# open-lab-VUSB-A.net
KiCad netlist of a schematic drawn in EAGLE
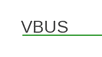
[diagram p0: schematic, sheet 1, part 1 of 2]
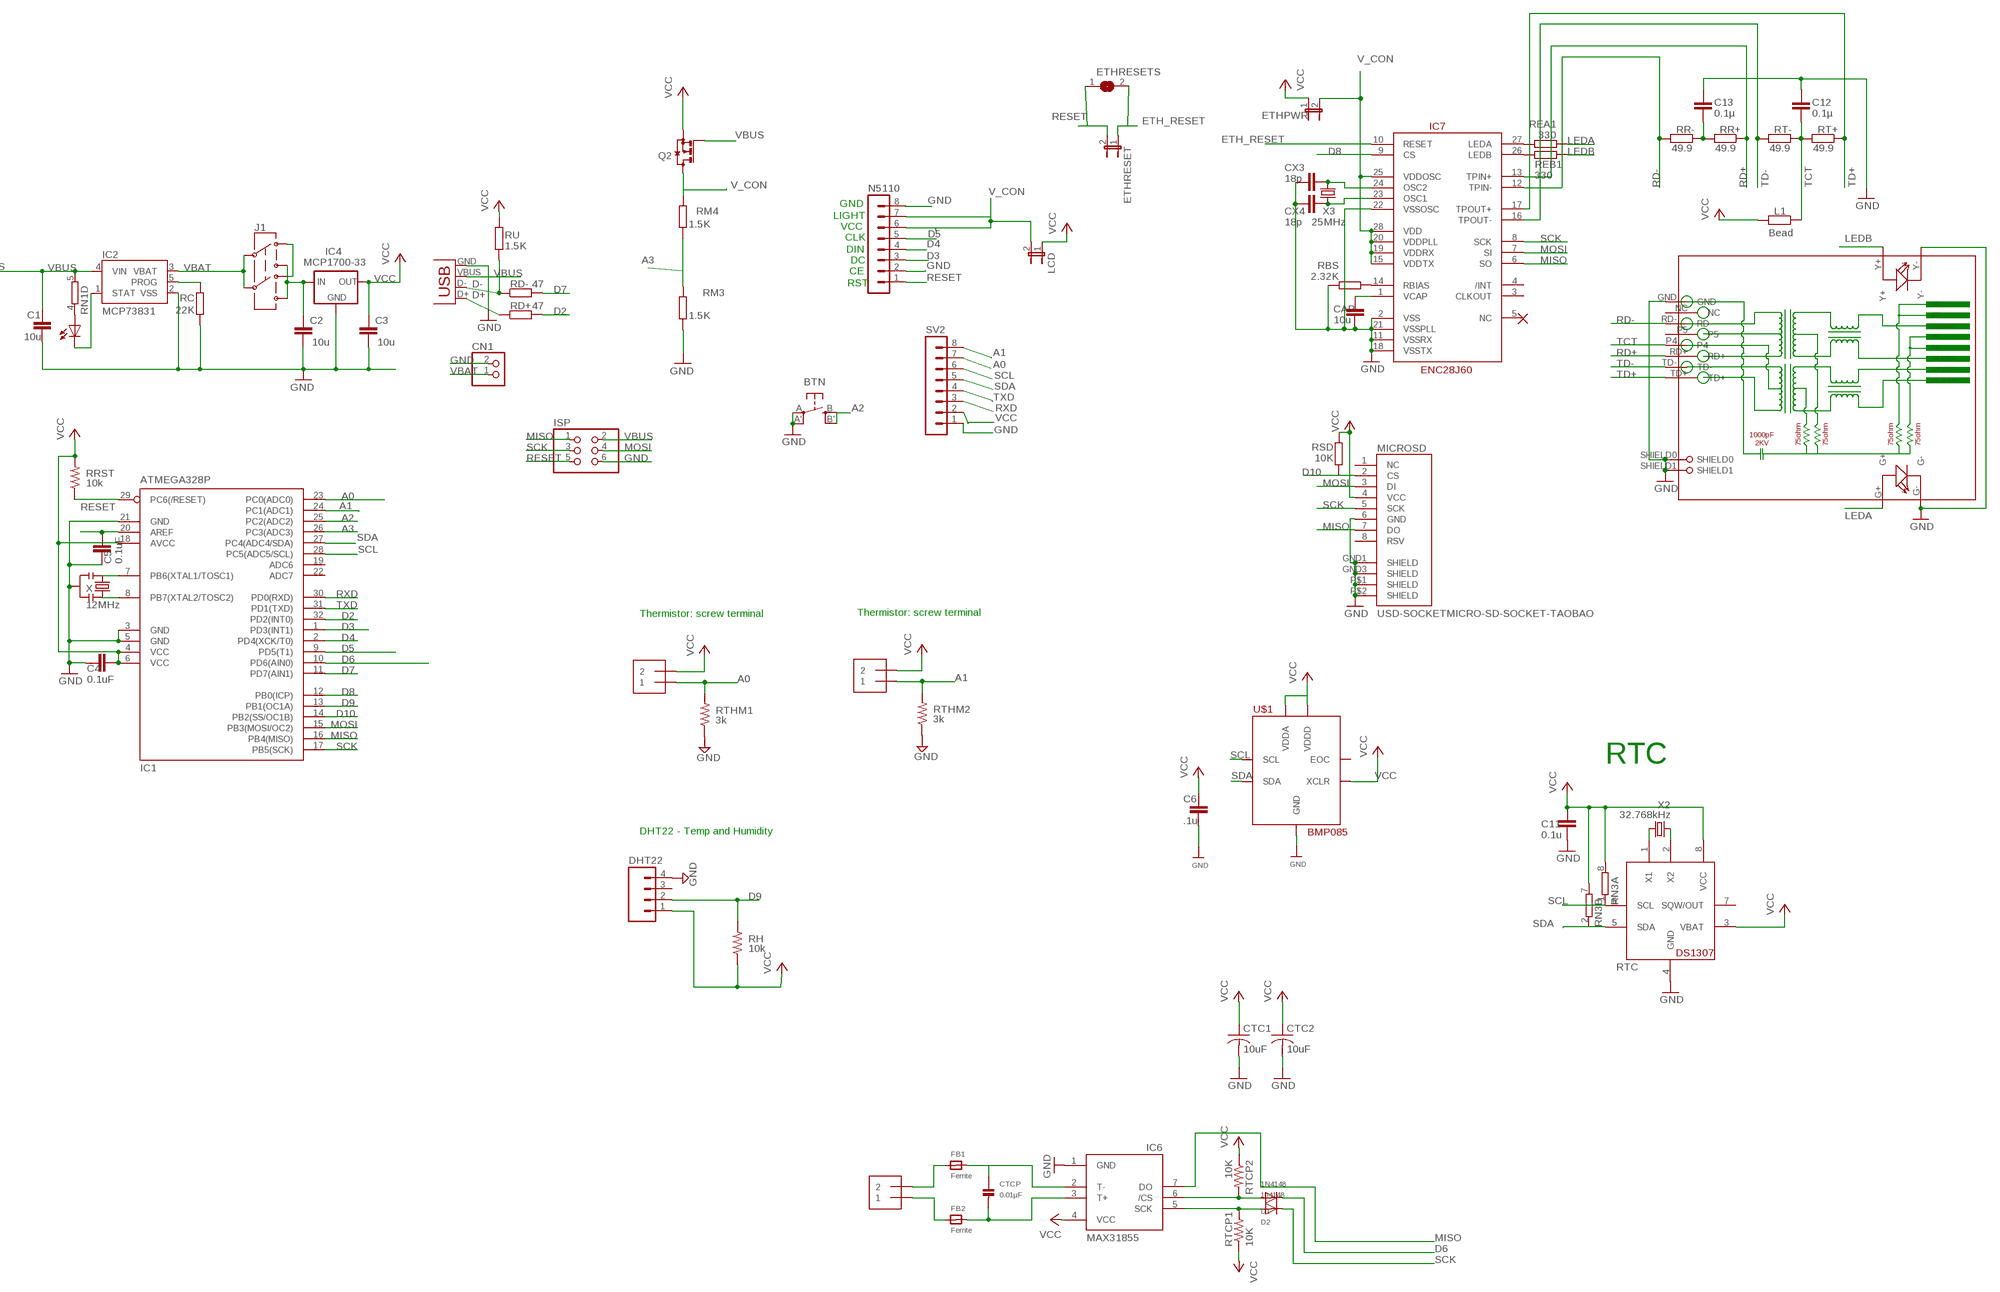
[diagram p1: schematic, sheet 1, part 2 of 2]

(export (version "E")
  (design (tool "Eeschema 10.0.6"))
  (components
    (comp (ref "BTN")
      (value "EVQQ2")
      (footprint "eagle-import:EVQ-Q2")
      (libsource (lib "eagle-import") (part "EVQQ2"))
    )
    (comp (ref "C1")
      (value "10u")
      (footprint "eagle-import:C0805")
      (libsource (lib "eagle-import") (part "resistor_C-EUC0805"))
    )
    (comp (ref "C2")
      (value "10u")
      (footprint "eagle-import:C0805")
      (libsource (lib "eagle-import") (part "resistor_C-EUC0805"))
    )
    (comp (ref "C3")
      (value "10u")
      (footprint "eagle-import:C0805")
      (libsource (lib "eagle-import") (part "resistor_C-EUC0805"))
    )
    (comp (ref "C4")
      (value "0.1uF")
      (footprint "eagle-import:C0805")
      (libsource (lib "eagle-import") (part "C-EUC0805"))
    )
    (comp (ref "C5")
      (value "0.1uF")
      (footprint "eagle-import:C0805")
      (libsource (lib "eagle-import") (part "C-EUC0805"))
    )
    (comp (ref "C6")
      (value ".1u")
      (footprint "eagle-import:C0805")
      (libsource (lib "eagle-import") (part "resistor_C-EUC0805"))
    )
    (comp (ref "C11")
      (value "0.1u")
      (footprint "eagle-import:C0805")
      (libsource (lib "eagle-import") (part "C-EUC0805"))
    )
    (comp (ref "C12")
      (value "0.1µ")
      (footprint "eagle-import:C0805")
      (libsource (lib "eagle-import") (part "resistor_C-EUC0805"))
    )
    (comp (ref "C13")
      (value "0.1µ")
      (footprint "eagle-import:C0805")
      (libsource (lib "eagle-import") (part "resistor_C-EUC0805"))
    )
    (comp (ref "CAP")
      (value "10u")
      (footprint "eagle-import:C0805")
      (libsource (lib "eagle-import") (part "resistor_C-EUC0805"))
    )
    (comp (ref "CHG")
      (value "0805")
      (footprint "eagle-import:CHIPLED_0805")
      (libsource (lib "eagle-import") (part "LEDCHIPLED_0805"))
    )
    (comp (ref "CN1")
      (value "JST_2PIN-SMT-RA")
      (footprint "eagle-import:JST-PH-2-SMT-RA")
      (libsource (lib "eagle-import") (part "JST_2PIN-SMT-RA"))
    )
    (comp (ref "CTC1")
      (value "10uF")
      (footprint "eagle-import:C0805K")
      (libsource (lib "eagle-import") (part "C-USC0805K"))
    )
    (comp (ref "CTC2")
      (value "10uF")
      (footprint "eagle-import:C0805K")
      (libsource (lib "eagle-import") (part "C-USC0805K"))
    )
    (comp (ref "CTCP")
      (value "0.01µF")
      (footprint "eagle-import:_0805")
      (libsource (lib "eagle-import") (part "CAP_CERAMIC_0805"))
    )
    (comp (ref "CX3")
      (value "18p")
      (footprint "eagle-import:C0805")
      (libsource (lib "eagle-import") (part "resistor_C-EUC0805"))
    )
    (comp (ref "CX4")
      (value "18p")
      (footprint "eagle-import:C0805")
      (libsource (lib "eagle-import") (part "resistor_C-EUC0805"))
    )
    (comp (ref "D1")
      (value "1N4148")
      (footprint "eagle-import:SOD-323F")
      (libsource (lib "eagle-import") (part "DIODESOD-323F"))
    )
    (comp (ref "D2")
      (value "1n4148")
      (footprint "eagle-import:SOD-323F")
      (libsource (lib "eagle-import") (part "DIODESOD-323F"))
    )
    (comp (ref "DHT22")
      (value "M04LOCK")
      (footprint "eagle-import:1X04_LOCK")
      (libsource (lib "eagle-import") (part "M04LOCK"))
    )
    (comp (ref "ETHPWR")
      (value "JP1E")
      (footprint "eagle-import:JP1")
      (libsource (lib "eagle-import") (part "JP1E"))
    )
    (comp (ref "ETHRESET")
      (value "JP1E")
      (footprint "eagle-import:JP1")
      (libsource (lib "eagle-import") (part "JP1E"))
    )
    (comp (ref "ETHRESETS")
      (value "SJ")
      (footprint "eagle-import:SJ")
      (libsource (lib "eagle-import") (part "SJ"))
    )
    (comp (ref "FB1")
      (value "Ferrite")
      (footprint "eagle-import:_0805")
      (libsource (lib "eagle-import") (part "FERRITE_0805"))
    )
    (comp (ref "FB2")
      (value "Ferrite")
      (footprint "eagle-import:_0805")
      (libsource (lib "eagle-import") (part "FERRITE_0805"))
    )
    (comp (ref "IC1")
      (value "ATMEGA328P")
      (footprint "eagle-import:TQFP32-08")
      (fields (field (name "MPN") "ATMEGA8-16AU"))
      (libsource (lib "eagle-import") (part "MEGA8-AI"))
    )
    (comp (ref "IC2")
      (value "MCP73831")
      (footprint "eagle-import:SOT23-5")
      (libsource (lib "eagle-import") (part "MCP73831"))
    )
    (comp (ref "IC4")
      (value "MCP1700-33")
      (footprint "eagle-import:SOT23")
      (libsource (lib "eagle-import") (part "MCP1700SOT233"))
    )
    (comp (ref "IC6")
      (value "MAX31855")
      (footprint "eagle-import:SO08")
      (libsource (lib "eagle-import") (part "MAX6675"))
    )
    (comp (ref "IC7")
      (value "ENC28J60")
      (footprint "eagle-import:SOIC28WLONG")
      (libsource (lib "eagle-import") (part "ENC28J60SO28LONG"))
    )
    (comp (ref "ISP")
      (value "PINHD-2X3")
      (footprint "eagle-import:2X03")
      (libsource (lib "eagle-import") (part "PINHD-2X3"))
    )
    (comp (ref "J1")
      (value "AYZ0202")
      (footprint "eagle-import:AYZ0202")
      (libsource (lib "eagle-import") (part "AYZ0202"))
    )
    (comp (ref "L1")
      (value "Bead")
      (footprint "eagle-import:R0805")
      (libsource (lib "eagle-import") (part "R-EU_R0805"))
    )
    (comp (ref "LCD")
      (value "JP1E")
      (footprint "eagle-import:JP1")
      (libsource (lib "eagle-import") (part "JP1E"))
    )
    (comp (ref "MICROSD")
      (value "USD-SOCKETMICRO-SD-SOCKET-TAOBAO")
      (footprint "eagle-import:MICRO-SD-SOCKET-TAOBAO")
      (libsource (lib "eagle-import") (part "USD-SOCKETMICRO-SD-SOCKET-TAOBAO"))
    )
    (comp (ref "N5110")
      (value "MA08-1")
      (footprint "eagle-import:MA08-1")
      (libsource (lib "eagle-import") (part "MA08-1"))
    )
    (comp (ref "Q2")
      (value "BSS123")
      (footprint "eagle-import:SOT23")
      (libsource (lib "eagle-import") (part "BSS123"))
    )
    (comp (ref "RBS")
      (value "2.32K")
      (footprint "eagle-import:R0805")
      (libsource (lib "eagle-import") (part "R-EU_R0805"))
    )
    (comp (ref "RC")
      (value "22K")
      (footprint "eagle-import:R0805")
      (libsource (lib "eagle-import") (part "R-EU_R0805"))
    )
    (comp (ref "RD+")
      (value "47")
      (footprint "eagle-import:R0805")
      (libsource (lib "eagle-import") (part "R-EU_R0805"))
    )
    (comp (ref "RD-")
      (value "47")
      (footprint "eagle-import:R0805")
      (libsource (lib "eagle-import") (part "R-EU_R0805"))
    )
    (comp (ref "REA1")
      (value "330")
      (footprint "eagle-import:R0805")
      (libsource (lib "eagle-import") (part "R-EU_R0805"))
    )
    (comp (ref "REB1")
      (value "330")
      (footprint "eagle-import:R0805")
      (libsource (lib "eagle-import") (part "R-EU_R0805"))
    )
    (comp (ref "RH")
      (value "10k")
      (footprint "eagle-import:R0805@1")
      (libsource (lib "eagle-import") (part "rcl_R-US_R0805"))
    )
    (comp (ref "RJ45")
      (value "HR911105A")
      (footprint "eagle-import:HR911105A")
      (libsource (lib "eagle-import") (part "HR911105A"))
    )
    (comp (ref "RM3")
      (value "1.5K")
      (footprint "eagle-import:R0805")
      (libsource (lib "eagle-import") (part "R-EU_R0805"))
    )
    (comp (ref "RM4")
      (value "1.5K")
      (footprint "eagle-import:R0805")
      (libsource (lib "eagle-import") (part "R-EU_R0805"))
    )
    (comp (ref "RN1")
      (value "4R-NEXB38V")
      (footprint "eagle-import:EXB38V")
      (libsource (lib "eagle-import") (part "4R-NEXB38V"))
    )
    (comp (ref "RN3")
      (value "4R-NEXB38V")
      (footprint "eagle-import:EXB38V")
      (libsource (lib "eagle-import") (part "4R-NEXB38V"))
    )
    (comp (ref "RR+")
      (value "49.9")
      (footprint "eagle-import:R0805")
      (libsource (lib "eagle-import") (part "R-EU_R0805"))
    )
    (comp (ref "RR-")
      (value "49.9")
      (footprint "eagle-import:R0805")
      (libsource (lib "eagle-import") (part "R-EU_R0805"))
    )
    (comp (ref "RRST")
      (value "10k")
      (footprint "eagle-import:R0805@1")
      (libsource (lib "eagle-import") (part "rcl_R-US_R0805"))
    )
    (comp (ref "RSD")
      (value "10K")
      (footprint "eagle-import:R0805")
      (libsource (lib "eagle-import") (part "R-EU_R0805"))
    )
    (comp (ref "RT+")
      (value "49.9")
      (footprint "eagle-import:R0805")
      (libsource (lib "eagle-import") (part "R-EU_R0805"))
    )
    (comp (ref "RT-")
      (value "49.9")
      (footprint "eagle-import:R0805")
      (libsource (lib "eagle-import") (part "R-EU_R0805"))
    )
    (comp (ref "RTC")
      (value "DS1307")
      (footprint "eagle-import:SO08")
      (libsource (lib "eagle-import") (part "DS1307SOIC"))
    )
    (comp (ref "RTCP1")
      (value "10K")
      (footprint "eagle-import:R0805")
      (libsource (lib "eagle-import") (part "R-US_R0805"))
    )
    (comp (ref "RTCP2")
      (value "10K")
      (footprint "eagle-import:R0805")
      (libsource (lib "eagle-import") (part "R-US_R0805"))
    )
    (comp (ref "RTHM1")
      (value "3k")
      (footprint "eagle-import:R0805@1")
      (libsource (lib "eagle-import") (part "rcl_R-US_R0805"))
    )
    (comp (ref "RTHM2")
      (value "3k")
      (footprint "eagle-import:R0805@1")
      (libsource (lib "eagle-import") (part "rcl_R-US_R0805"))
    )
    (comp (ref "RU")
      (value "1.5K")
      (footprint "eagle-import:R0805")
      (libsource (lib "eagle-import") (part "R-EU_R0805"))
    )
    (comp (ref "SV2")
      (value "MA08-1")
      (footprint "eagle-import:MA08-1")
      (libsource (lib "eagle-import") (part "MA08-1"))
    )
    (comp (ref "TCPL")
      (value "1X2-3.5MM")
      (footprint "eagle-import:1X2-3.5MM")
      (libsource (lib "eagle-import") (part "1X2-3.5MM"))
    )
    (comp (ref "THM1")
      (value "1X2-3.5MM")
      (footprint "eagle-import:1X2-3.5MM")
      (libsource (lib "eagle-import") (part "1X2-3.5MM"))
    )
    (comp (ref "THM2")
      (value "1X2-3.5MM")
      (footprint "eagle-import:1X2-3.5MM")
      (libsource (lib "eagle-import") (part "1X2-3.5MM"))
    )
    (comp (ref "U$1")
      (value "BMP085")
      (footprint "eagle-import:BMP085")
      (libsource (lib "eagle-import") (part "BMP085"))
    )
    (comp (ref "X")
      (value "12MHz")
      (footprint "eagle-import:RESONATOR-SMD")
      (libsource (lib "eagle-import") (part "RESONATORSMD"))
    )
    (comp (ref "X1")
      (value "USBSMD")
      (footprint "eagle-import:USB-MINIB")
      (libsource (lib "eagle-import") (part "USBSMD"))
    )
    (comp (ref "X2")
      (value "32.768kHz")
      (footprint "eagle-import:TC26H")
      (libsource (lib "eagle-import") (part "crystal_CRYSTALTC26H"))
    )
    (comp (ref "X3")
      (value "25MHz")
      (footprint "eagle-import:HC49U-V")
      (libsource (lib "eagle-import") (part "CRYSTALHC49UV"))
    )
  )
  (nets
    (net (code "1") (name "/A0") (class "Default")
      (node (ref "IC1") (pin "23") (pinfunction "PC0(ADC0)_23") (pintype "bidirectional"))
      (node (ref "RTHM1") (pin "2") (pinfunction "2_2") (pintype "passive"))
      (node (ref "SV2") (pin "7") (pinfunction "7_7") (pintype "passive"))
      (node (ref "THM1") (pin "1") (pinfunction "1_1") (pintype "passive"))
    )
    (net (code "2") (name "/A1") (class "Default")
      (node (ref "IC1") (pin "24") (pinfunction "PC1(ADC1)_24") (pintype "bidirectional"))
      (node (ref "RTHM2") (pin "2") (pinfunction "2_2") (pintype "passive"))
      (node (ref "SV2") (pin "8") (pinfunction "8_8") (pintype "passive"))
      (node (ref "THM2") (pin "1") (pinfunction "1_1") (pintype "passive"))
    )
    (net (code "3") (name "/A2") (class "Default")
      (node (ref "BTN") (pin "B") (pinfunction "S_B") (pintype "passive"))
      (node (ref "BTN") (pin "B'") (pinfunction "S1_B'") (pintype "passive"))
      (node (ref "IC1") (pin "25") (pinfunction "PC2(ADC2)_25") (pintype "bidirectional"))
    )
    (net (code "4") (name "/A3") (class "Default")
      (node (ref "IC1") (pin "26") (pinfunction "PC3(ADC3)_26") (pintype "bidirectional"))
      (node (ref "RM3") (pin "2") (pinfunction "2_2") (pintype "passive"))
      (node (ref "RM4") (pin "1") (pinfunction "1_1") (pintype "passive"))
    )
    (net (code "5") (name "/D+") (class "Default")
      (node (ref "RD+") (pin "1") (pinfunction "1_1") (pintype "passive"))
      (node (ref "X1") (pin "D+") (pinfunction "D+_D+") (pintype "bidirectional"))
    )
    (net (code "6") (name "/D-") (class "Default")
      (node (ref "RD-") (pin "1") (pinfunction "1_1") (pintype "passive"))
      (node (ref "RU") (pin "1") (pinfunction "1_1") (pintype "passive"))
      (node (ref "X1") (pin "D-") (pinfunction "D-_D-") (pintype "bidirectional"))
    )
    (net (code "7") (name "/D2") (class "Default")
      (node (ref "IC1") (pin "32") (pinfunction "PD2(INT0)_32") (pintype "bidirectional"))
      (node (ref "RD+") (pin "2") (pinfunction "2_2") (pintype "passive"))
    )
    (net (code "8") (name "/D3") (class "Default")
      (node (ref "IC1") (pin "1") (pinfunction "PD3(INT1)_1") (pintype "bidirectional"))
      (node (ref "N5110") (pin "3") (pinfunction "3_3") (pintype "passive"))
    )
    (net (code "9") (name "/D4") (class "Default")
      (node (ref "IC1") (pin "2") (pinfunction "PD4(XCK/T0)_2") (pintype "bidirectional"))
      (node (ref "N5110") (pin "4") (pinfunction "4_4") (pintype "passive"))
    )
    (net (code "10") (name "/D5") (class "Default")
      (node (ref "IC1") (pin "9") (pinfunction "PD5(T1)_9") (pintype "bidirectional"))
      (node (ref "N5110") (pin "5") (pinfunction "5_5") (pintype "passive"))
    )
    (net (code "11") (name "/D6") (class "Default")
      (node (ref "D1") (pin "C") (pinfunction "C_C") (pintype "passive"))
      (node (ref "IC1") (pin "10") (pinfunction "PD6(AIN0)_10") (pintype "bidirectional"))
    )
    (net (code "12") (name "/D7") (class "Default")
      (node (ref "IC1") (pin "11") (pinfunction "PD7(AIN1)_11") (pintype "bidirectional"))
      (node (ref "RD-") (pin "2") (pinfunction "2_2") (pintype "passive"))
    )
    (net (code "13") (name "/D8") (class "Default")
      (node (ref "IC1") (pin "12") (pinfunction "PB0(ICP)_12") (pintype "bidirectional"))
      (node (ref "IC7") (pin "9") (pinfunction "CS_9") (pintype "bidirectional"))
    )
    (net (code "14") (name "/D9") (class "Default")
      (node (ref "DHT22") (pin "2") (pinfunction "2_2") (pintype "passive"))
      (node (ref "IC1") (pin "13") (pinfunction "PB1(OC1A)_13") (pintype "bidirectional"))
      (node (ref "RH") (pin "2") (pinfunction "2_2") (pintype "passive"))
    )
    (net (code "15") (name "/D10") (class "Default")
      (node (ref "IC1") (pin "14") (pinfunction "PB2(SS/OC1B)_14") (pintype "bidirectional"))
      (node (ref "MICROSD") (pin "2") (pinfunction "CS_2") (pintype "bidirectional"))
      (node (ref "RSD") (pin "1") (pinfunction "1_1") (pintype "passive"))
    )
    (net (code "16") (name "/ETH_RESET") (class "Default")
      (node (ref "ETHRESET") (pin "1") (pinfunction "1_1") (pintype "passive"))
      (node (ref "ETHRESETS") (pin "2") (pinfunction "2_2") (pintype "passive"))
      (node (ref "IC7") (pin "10") (pinfunction "RESET_10") (pintype "bidirectional"))
    )
    (net (code "17") (name "/LEDA") (class "Default")
      (node (ref "REA1") (pin "2") (pinfunction "2_2") (pintype "passive"))
      (node (ref "RJ45") (pin "G+") (pinfunction "G+_G+") (pintype "bidirectional"))
    )
    (net (code "18") (name "/LEDB") (class "Default")
      (node (ref "REB1") (pin "2") (pinfunction "2_2") (pintype "passive"))
      (node (ref "RJ45") (pin "Y+") (pinfunction "Y+_Y+") (pintype "bidirectional"))
    )
    (net (code "19") (name "/MISO") (class "Default")
      (node (ref "IC1") (pin "16") (pinfunction "PB4(MISO)_16") (pintype "bidirectional"))
      (node (ref "IC6") (pin "7") (pinfunction "DO_7") (pintype "output"))
      (node (ref "IC7") (pin "6") (pinfunction "SO_6") (pintype "bidirectional"))
      (node (ref "ISP") (pin "1") (pinfunction "1_1") (pintype "passive"))
      (node (ref "MICROSD") (pin "7") (pinfunction "DO_7") (pintype "bidirectional"))
    )
    (net (code "20") (name "/MOSI") (class "Default")
      (node (ref "IC1") (pin "15") (pinfunction "PB3(MOSI/OC2)_15") (pintype "bidirectional"))
      (node (ref "IC7") (pin "7") (pinfunction "SI_7") (pintype "bidirectional"))
      (node (ref "ISP") (pin "4") (pinfunction "4_4") (pintype "passive"))
      (node (ref "MICROSD") (pin "3") (pinfunction "DI_3") (pintype "bidirectional"))
    )
    (net (code "21") (name "/RD+") (class "Default")
      (node (ref "IC7") (pin "13") (pinfunction "TPIN+_13") (pintype "bidirectional"))
      (node (ref "RJ45") (pin "RD+") (pinfunction "RD+_RD+") (pintype "bidirectional"))
      (node (ref "RR+") (pin "1") (pinfunction "1_1") (pintype "passive"))
    )
    (net (code "22") (name "/RD-") (class "Default")
      (node (ref "IC7") (pin "12") (pinfunction "TPIN-_12") (pintype "bidirectional"))
      (node (ref "RJ45") (pin "RD-") (pinfunction "RD-_RD-") (pintype "bidirectional"))
      (node (ref "RR-") (pin "2") (pinfunction "2_2") (pintype "passive"))
    )
    (net (code "23") (name "/RESET") (class "Default")
      (node (ref "ETHRESET") (pin "2") (pinfunction "2_2") (pintype "passive"))
      (node (ref "ETHRESETS") (pin "1") (pinfunction "1_1") (pintype "passive"))
      (node (ref "IC1") (pin "29") (pinfunction "PC6(/RESET)_29") (pintype "bidirectional"))
      (node (ref "ISP") (pin "5") (pinfunction "5_5") (pintype "passive"))
      (node (ref "N5110") (pin "1") (pinfunction "1_1") (pintype "passive"))
      (node (ref "RRST") (pin "1") (pinfunction "1_1") (pintype "passive"))
    )
    (net (code "24") (name "/RXD") (class "Default")
      (node (ref "IC1") (pin "30") (pinfunction "PD0(RXD)_30") (pintype "bidirectional"))
      (node (ref "SV2") (pin "3") (pinfunction "3_3") (pintype "passive"))
    )
    (net (code "25") (name "/SCK") (class "Default")
      (node (ref "D2") (pin "C") (pinfunction "C_C") (pintype "passive"))
      (node (ref "IC1") (pin "17") (pinfunction "PB5(SCK)_17") (pintype "bidirectional"))
      (node (ref "IC7") (pin "8") (pinfunction "SCK_8") (pintype "bidirectional"))
      (node (ref "ISP") (pin "3") (pinfunction "3_3") (pintype "passive"))
      (node (ref "MICROSD") (pin "5") (pinfunction "SCK_5") (pintype "bidirectional"))
    )
    (net (code "26") (name "/SCL") (class "Default")
      (node (ref "IC1") (pin "28") (pinfunction "PC5(ADC5/SCL)_28") (pintype "bidirectional"))
      (node (ref "RN3") (pin "1") (pinfunction "1_1") (pintype "passive"))
      (node (ref "RTC") (pin "6") (pinfunction "SCL_6") (pintype "bidirectional"))
      (node (ref "SV2") (pin "6") (pinfunction "6_6") (pintype "passive"))
      (node (ref "U$1") (pin "P$6") (pinfunction "SCL_P$6") (pintype "bidirectional"))
    )
    (net (code "27") (name "/SDA") (class "Default")
      (node (ref "IC1") (pin "27") (pinfunction "PC4(ADC4/SDA)_27") (pintype "bidirectional"))
      (node (ref "RN3") (pin "2") (pinfunction "1_2") (pintype "passive"))
      (node (ref "RTC") (pin "5") (pinfunction "SDA_5") (pintype "bidirectional"))
      (node (ref "SV2") (pin "5") (pinfunction "5_5") (pintype "passive"))
      (node (ref "U$1") (pin "P$7") (pinfunction "SDA_P$7") (pintype "bidirectional"))
    )
    (net (code "28") (name "/TCT") (class "Default")
      (node (ref "C12") (pin "2") (pinfunction "2_2") (pintype "passive"))
      (node (ref "L1") (pin "1") (pinfunction "1_1") (pintype "passive"))
      (node (ref "RJ45") (pin "P4") (pinfunction "P4_P4") (pintype "bidirectional"))
      (node (ref "RT+") (pin "2") (pinfunction "2_2") (pintype "passive"))
      (node (ref "RT-") (pin "1") (pinfunction "1_1") (pintype "passive"))
    )
    (net (code "29") (name "/TD+") (class "Default")
      (node (ref "IC7") (pin "17") (pinfunction "TPOUT+_17") (pintype "bidirectional"))
      (node (ref "RJ45") (pin "TD+") (pinfunction "TD+_TD+") (pintype "bidirectional"))
      (node (ref "RT+") (pin "1") (pinfunction "1_1") (pintype "passive"))
    )
    (net (code "30") (name "/TD-") (class "Default")
      (node (ref "IC7") (pin "16") (pinfunction "TPOUT-_16") (pintype "bidirectional"))
      (node (ref "RJ45") (pin "TD-") (pinfunction "TD-_TD-") (pintype "bidirectional"))
      (node (ref "RT-") (pin "2") (pinfunction "2_2") (pintype "passive"))
    )
    (net (code "31") (name "/TXD") (class "Default")
      (node (ref "IC1") (pin "31") (pinfunction "PD1(TXD)_31") (pintype "bidirectional"))
      (node (ref "SV2") (pin "4") (pinfunction "4_4") (pintype "passive"))
    )
    (net (code "32") (name "/VBAT") (class "Default")
      (node (ref "CN1") (pin "1") (pinfunction "2_1") (pintype "passive"))
      (node (ref "IC2") (pin "3") (pinfunction "VBAT_3") (pintype "power_in"))
      (node (ref "J1") (pin "2") (pinfunction "2_2") (pintype "bidirectional"))
      (node (ref "J1") (pin "5") (pinfunction "5_5") (pintype "bidirectional"))
    )
    (net (code "33") (name "/VBUS") (class "Default")
      (node (ref "C1") (pin "1") (pinfunction "1_1") (pintype "passive"))
      (node (ref "IC2") (pin "4") (pinfunction "VIN_4") (pintype "power_in"))
      (node (ref "ISP") (pin "2") (pinfunction "2_2") (pintype "passive"))
      (node (ref "Q2") (pin "1") (pinfunction "G_1") (pintype "passive"))
      (node (ref "RN1") (pin "5") (pinfunction "2_5") (pintype "passive"))
      (node (ref "X1") (pin "VBUS") (pinfunction "VBUS_VBUS") (pintype "bidirectional"))
    )
    (net (code "34") (name "/V_CON") (class "Default")
      (node (ref "ETHPWR") (pin "2") (pinfunction "2_2") (pintype "passive"))
      (node (ref "IC7") (pin "15") (pinfunction "VDDTX_15") (pintype "bidirectional"))
      (node (ref "IC7") (pin "19") (pinfunction "VDDRX_19") (pintype "bidirectional"))
      (node (ref "IC7") (pin "20") (pinfunction "VDDPLL_20") (pintype "bidirectional"))
      (node (ref "IC7") (pin "25") (pinfunction "VDDOSC_25") (pintype "bidirectional"))
      (node (ref "IC7") (pin "28") (pinfunction "VDD_28") (pintype "bidirectional"))
      (node (ref "LCD") (pin "2") (pinfunction "2_2") (pintype "passive"))
      (node (ref "N5110") (pin "6") (pinfunction "6_6") (pintype "passive"))
      (node (ref "N5110") (pin "7") (pinfunction "7_7") (pintype "passive"))
      (node (ref "Q2") (pin "3") (pinfunction "D_3") (pintype "passive"))
      (node (ref "RM4") (pin "2") (pinfunction "2_2") (pintype "passive"))
    )
    (net (code "35") (name "GND") (class "Default")
      (node (ref "BTN") (pin "A") (pinfunction "P_A") (pintype "passive"))
      (node (ref "BTN") (pin "A'") (pinfunction "P1_A'") (pintype "passive"))
      (node (ref "C1") (pin "2") (pinfunction "2_2") (pintype "passive"))
      (node (ref "C11") (pin "2") (pinfunction "2_2") (pintype "passive"))
      (node (ref "C12") (pin "1") (pinfunction "1_1") (pintype "passive"))
      (node (ref "C13") (pin "1") (pinfunction "1_1") (pintype "passive"))
      (node (ref "C2") (pin "2") (pinfunction "2_2") (pintype "passive"))
      (node (ref "C3") (pin "2") (pinfunction "2_2") (pintype "passive"))
      (node (ref "C4") (pin "1") (pinfunction "1_1") (pintype "passive"))
      (node (ref "C5") (pin "1") (pinfunction "1_1") (pintype "passive"))
      (node (ref "C6") (pin "2") (pinfunction "2_2") (pintype "passive"))
      (node (ref "CAP") (pin "2") (pinfunction "2_2") (pintype "passive"))
      (node (ref "CN1") (pin "2") (pinfunction "1_2") (pintype "passive"))
      (node (ref "CTC1") (pin "2") (pinfunction "2_2") (pintype "passive"))
      (node (ref "CTC2") (pin "2") (pinfunction "2_2") (pintype "passive"))
      (node (ref "CX3") (pin "2") (pinfunction "2_2") (pintype "passive"))
      (node (ref "CX4") (pin "2") (pinfunction "2_2") (pintype "passive"))
      (node (ref "DHT22") (pin "4") (pinfunction "4_4") (pintype "passive"))
      (node (ref "IC1") (pin "21") (pinfunction "GND_21") (pintype "power_in"))
      (node (ref "IC1") (pin "3") (pinfunction "GND_3") (pintype "power_in"))
      (node (ref "IC1") (pin "5") (pinfunction "GND_5") (pintype "power_in"))
      (node (ref "IC2") (pin "2") (pinfunction "VSS_2") (pintype "power_in"))
      (node (ref "IC4") (pin "1") (pinfunction "GND_1") (pintype "input"))
      (node (ref "IC6") (pin "1") (pinfunction "GND_1") (pintype "power_in"))
      (node (ref "IC7") (pin "11") (pinfunction "VSSRX_11") (pintype "bidirectional"))
      (node (ref "IC7") (pin "18") (pinfunction "VSSTX_18") (pintype "bidirectional"))
      (node (ref "IC7") (pin "2") (pinfunction "VSS_2") (pintype "bidirectional"))
      (node (ref "IC7") (pin "21") (pinfunction "VSSPLL_21") (pintype "bidirectional"))
      (node (ref "IC7") (pin "22") (pinfunction "VSSOSC_22") (pintype "bidirectional"))
      (node (ref "ISP") (pin "6") (pinfunction "6_6") (pintype "passive"))
      (node (ref "MICROSD") (pin "6") (pinfunction "GND_6") (pintype "bidirectional"))
      (node (ref "MICROSD") (pin "GND1") (pinfunction "SHIELD_GND1") (pintype "bidirectional"))
      (node (ref "MICROSD") (pin "GND3") (pinfunction "SHIELD_GND3") (pintype "bidirectional"))
      (node (ref "MICROSD") (pin "P$1") (pinfunction "SHIELD_P$1") (pintype "bidirectional"))
      (node (ref "MICROSD") (pin "P$2") (pinfunction "SHIELD_P$2") (pintype "bidirectional"))
      (node (ref "N5110") (pin "2") (pinfunction "2_2") (pintype "passive"))
      (node (ref "RBS") (pin "1") (pinfunction "1_1") (pintype "passive"))
      (node (ref "RC") (pin "1") (pinfunction "1_1") (pintype "passive"))
      (node (ref "RJ45") (pin "G-") (pinfunction "G-_G-") (pintype "bidirectional"))
      (node (ref "RJ45") (pin "GND") (pinfunction "GND_GND") (pintype "bidirectional"))
      (node (ref "RJ45") (pin "SHIELD0") (pinfunction "SHIELD0_SHIELD0") (pintype "bidirectional"))
      (node (ref "RJ45") (pin "SHIELD1") (pinfunction "SHIELD1_SHIELD1") (pintype "bidirectional"))
      (node (ref "RJ45") (pin "Y-") (pinfunction "Y-_Y-") (pintype "bidirectional"))
      (node (ref "RM3") (pin "1") (pinfunction "1_1") (pintype "passive"))
      (node (ref "RTC") (pin "4") (pinfunction "GND_4") (pintype "power_in"))
      (node (ref "RTHM1") (pin "1") (pinfunction "1_1") (pintype "passive"))
      (node (ref "RTHM2") (pin "1") (pinfunction "1_1") (pintype "passive"))
      (node (ref "SV2") (pin "1") (pinfunction "1_1") (pintype "passive"))
      (node (ref "U$1") (pin "P$1") (pinfunction "GND_P$1") (pintype "power_in"))
      (node (ref "X") (pin "2") (pinfunction "2_2") (pintype "passive"))
      (node (ref "X1") (pin "GND") (pinfunction "GND_GND") (pintype "bidirectional"))
    )
    (net (code "36") (name "Net-(C13-Pad2)") (class "Default")
      (node (ref "C13") (pin "2") (pinfunction "2_2") (pintype "passive"))
      (node (ref "RR+") (pin "2") (pinfunction "2_2") (pintype "passive"))
      (node (ref "RR-") (pin "1") (pinfunction "1_1") (pintype "passive"))
    )
    (net (code "37") (name "Net-(CTCP-P$1)") (class "Default")
      (node (ref "CTCP") (pin "1") (pinfunction "P$1_1") (pintype "passive"))
      (node (ref "FB1") (pin "2") (pinfunction "P$2_2") (pintype "passive"))
      (node (ref "IC6") (pin "2") (pinfunction "T-_2") (pintype "input"))
    )
    (net (code "38") (name "Net-(CTCP-P$2)") (class "Default")
      (node (ref "CTCP") (pin "2") (pinfunction "P$2_2") (pintype "passive"))
      (node (ref "FB2") (pin "2") (pinfunction "P$2_2") (pintype "passive"))
      (node (ref "IC6") (pin "3") (pinfunction "T+_3") (pintype "input"))
    )
    (net (code "39") (name "Net-(FB1-P$1)") (class "Default")
      (node (ref "FB1") (pin "1") (pinfunction "P$1_1") (pintype "passive"))
      (node (ref "TCPL") (pin "2") (pinfunction "2_2") (pintype "passive"))
    )
    (net (code "40") (name "Net-(FB2-P$1)") (class "Default")
      (node (ref "FB2") (pin "1") (pinfunction "P$1_1") (pintype "passive"))
      (node (ref "TCPL") (pin "1") (pinfunction "1_1") (pintype "passive"))
    )
    (net (code "41") (name "Net-(IC1-AREF)") (class "Default")
      (node (ref "C5") (pin "2") (pinfunction "2_2") (pintype "passive"))
      (node (ref "IC1") (pin "20") (pinfunction "AREF_20") (pintype "passive"))
    )
    (net (code "42") (name "Net-(IC1-PB6(XTAL1{slash}TOSC1))") (class "Default")
      (node (ref "IC1") (pin "7") (pinfunction "PB6(XTAL1/TOSC1)_7") (pintype "bidirectional"))
      (node (ref "X") (pin "1") (pinfunction "1_1") (pintype "passive"))
    )
    (net (code "43") (name "Net-(IC1-PB7(XTAL2{slash}TOSC2))") (class "Default")
      (node (ref "IC1") (pin "8") (pinfunction "PB7(XTAL2/TOSC2)_8") (pintype "bidirectional"))
      (node (ref "X") (pin "3") (pinfunction "3_3") (pintype "passive"))
    )
    (net (code "44") (name "Net-(IC2-PROG)") (class "Default")
      (node (ref "IC2") (pin "5") (pinfunction "PROG_5") (pintype "input"))
      (node (ref "RC") (pin "2") (pinfunction "2_2") (pintype "passive"))
    )
    (net (code "45") (name "Net-(IC2-STAT)") (class "Default")
      (node (ref "CHG") (pin "C") (pinfunction "C_C") (pintype "passive"))
      (node (ref "IC2") (pin "1") (pinfunction "STAT_1") (pintype "output"))
    )
    (net (code "46") (name "Net-(IC4-IN)") (class "Default")
      (node (ref "C2") (pin "1") (pinfunction "1_1") (pintype "passive"))
      (node (ref "IC4") (pin "3") (pinfunction "IN_3") (pintype "input"))
      (node (ref "J1") (pin "1") (pinfunction "3_1") (pintype "bidirectional"))
      (node (ref "J1") (pin "4") (pinfunction "6_4") (pintype "bidirectional"))
    )
    (net (code "47") (name "Net-(IC6-SCK)") (class "Default")
      (node (ref "D2") (pin "A") (pinfunction "A_A") (pintype "passive"))
      (node (ref "IC6") (pin "5") (pinfunction "SCK_5") (pintype "input"))
      (node (ref "RTCP1") (pin "2") (pinfunction "2_2") (pintype "passive"))
    )
    (net (code "48") (name "Net-(IC6-{slash}CS)") (class "Default")
      (node (ref "D1") (pin "A") (pinfunction "A_A") (pintype "passive"))
      (node (ref "IC6") (pin "6") (pinfunction "/CS_6") (pintype "input"))
      (node (ref "RTCP2") (pin "2") (pinfunction "2_2") (pintype "passive"))
    )
    (net (code "49") (name "Net-(IC7-LEDA)") (class "Default")
      (node (ref "IC7") (pin "27") (pinfunction "LEDA_27") (pintype "bidirectional"))
      (node (ref "REA1") (pin "1") (pinfunction "1_1") (pintype "passive"))
    )
    (net (code "50") (name "Net-(IC7-LEDB)") (class "Default")
      (node (ref "IC7") (pin "26") (pinfunction "LEDB_26") (pintype "bidirectional"))
      (node (ref "REB1") (pin "1") (pinfunction "1_1") (pintype "passive"))
    )
    (net (code "51") (name "Net-(IC7-OSC1)") (class "Default")
      (node (ref "CX4") (pin "1") (pinfunction "1_1") (pintype "passive"))
      (node (ref "IC7") (pin "23") (pinfunction "OSC1_23") (pintype "bidirectional"))
      (node (ref "X3") (pin "1") (pinfunction "1_1") (pintype "passive"))
    )
    (net (code "52") (name "Net-(IC7-OSC2)") (class "Default")
      (node (ref "CX3") (pin "1") (pinfunction "1_1") (pintype "passive"))
      (node (ref "IC7") (pin "24") (pinfunction "OSC2_24") (pintype "bidirectional"))
      (node (ref "X3") (pin "2") (pinfunction "2_2") (pintype "passive"))
    )
    (net (code "53") (name "Net-(IC7-RBIAS)") (class "Default")
      (node (ref "IC7") (pin "14") (pinfunction "RBIAS_14") (pintype "bidirectional"))
      (node (ref "RBS") (pin "2") (pinfunction "2_2") (pintype "passive"))
    )
    (net (code "54") (name "Net-(IC7-VCAP)") (class "Default")
      (node (ref "CAP") (pin "1") (pinfunction "1_1") (pintype "passive"))
      (node (ref "IC7") (pin "1") (pinfunction "VCAP_1") (pintype "bidirectional"))
    )
    (net (code "55") (name "Net-(J1-1)") (class "Default")
      (node (ref "J1") (pin "3") (pinfunction "1_3") (pintype "bidirectional"))
      (node (ref "J1") (pin "6") (pinfunction "4_6") (pintype "bidirectional"))
    )
    (net (code "56") (name "Net-(RN1D-1)") (class "Default")
      (node (ref "CHG") (pin "A") (pinfunction "A_A") (pintype "passive"))
      (node (ref "RN1") (pin "4") (pinfunction "1_4") (pintype "passive"))
    )
    (net (code "57") (name "Net-(RTC-X1)") (class "Default")
      (node (ref "RTC") (pin "1") (pinfunction "X1_1") (pintype "passive"))
      (node (ref "X2") (pin "2") (pinfunction "2_2") (pintype "passive"))
    )
    (net (code "58") (name "Net-(RTC-X2)") (class "Default")
      (node (ref "RTC") (pin "2") (pinfunction "X2_2") (pintype "passive"))
      (node (ref "X2") (pin "1") (pinfunction "1_1") (pintype "passive"))
    )
    (net (code "59") (name "VCC") (class "Default")
      (node (ref "C11") (pin "1") (pinfunction "1_1") (pintype "passive"))
      (node (ref "C3") (pin "1") (pinfunction "1_1") (pintype "passive"))
      (node (ref "C4") (pin "2") (pinfunction "2_2") (pintype "passive"))
      (node (ref "C6") (pin "1") (pinfunction "1_1") (pintype "passive"))
      (node (ref "CTC1") (pin "1") (pinfunction "1_1") (pintype "passive"))
      (node (ref "CTC2") (pin "1") (pinfunction "1_1") (pintype "passive"))
      (node (ref "DHT22") (pin "1") (pinfunction "1_1") (pintype "passive"))
      (node (ref "ETHPWR") (pin "1") (pinfunction "1_1") (pintype "passive"))
      (node (ref "IC1") (pin "18") (pinfunction "AVCC_18") (pintype "power_in"))
      (node (ref "IC1") (pin "4") (pinfunction "VCC_4") (pintype "power_in"))
      (node (ref "IC1") (pin "6") (pinfunction "VCC_6") (pintype "power_in"))
      (node (ref "IC4") (pin "2") (pinfunction "OUT_2") (pintype "passive"))
      (node (ref "IC6") (pin "4") (pinfunction "VCC_4") (pintype "power_in"))
      (node (ref "L1") (pin "2") (pinfunction "2_2") (pintype "passive"))
      (node (ref "LCD") (pin "1") (pinfunction "1_1") (pintype "passive"))
      (node (ref "MICROSD") (pin "4") (pinfunction "VCC_4") (pintype "bidirectional"))
      (node (ref "Q2") (pin "2") (pinfunction "S_2") (pintype "passive"))
      (node (ref "RH") (pin "1") (pinfunction "1_1") (pintype "passive"))
      (node (ref "RN3") (pin "7") (pinfunction "2_7") (pintype "passive"))
      (node (ref "RN3") (pin "8") (pinfunction "2_8") (pintype "passive"))
      (node (ref "RRST") (pin "2") (pinfunction "2_2") (pintype "passive"))
      (node (ref "RSD") (pin "2") (pinfunction "2_2") (pintype "passive"))
      (node (ref "RTC") (pin "3") (pinfunction "VBAT_3") (pintype "power_in"))
      (node (ref "RTC") (pin "8") (pinfunction "VCC_8") (pintype "power_in"))
      (node (ref "RTCP1") (pin "1") (pinfunction "1_1") (pintype "passive"))
      (node (ref "RTCP2") (pin "1") (pinfunction "1_1") (pintype "passive"))
      (node (ref "RU") (pin "2") (pinfunction "2_2") (pintype "passive"))
      (node (ref "SV2") (pin "2") (pinfunction "2_2") (pintype "passive"))
      (node (ref "THM1") (pin "2") (pinfunction "2_2") (pintype "passive"))
      (node (ref "THM2") (pin "2") (pinfunction "2_2") (pintype "passive"))
      (node (ref "U$1") (pin "P$3") (pinfunction "VDDA_P$3") (pintype "bidirectional"))
      (node (ref "U$1") (pin "P$4") (pinfunction "VDDD_P$4") (pintype "bidirectional"))
      (node (ref "U$1") (pin "P$8") (pinfunction "XCLR_P$8") (pintype "bidirectional"))
    )
    (net (code "60") (name "unconnected-(DHT22-Pad3)") (class "Default")
      (node (ref "DHT22") (pin "3") (pinfunction "3_3") (pintype "passive"))
    )
    (net (code "61") (name "unconnected-(IC1-ADC6-Pad19)") (class "Default")
      (node (ref "IC1") (pin "19") (pinfunction "ADC6_19") (pintype "bidirectional"))
    )
    (net (code "62") (name "unconnected-(IC1-ADC7-Pad22)") (class "Default")
      (node (ref "IC1") (pin "22") (pinfunction "ADC7_22") (pintype "bidirectional"))
    )
    (net (code "63") (name "unconnected-(IC7-CLKOUT-Pad3)") (class "Default")
      (node (ref "IC7") (pin "3") (pinfunction "CLKOUT_3") (pintype "bidirectional"))
    )
    (net (code "64") (name "unconnected-(IC7-NC-Pad5)") (class "Default")
      (node (ref "IC7") (pin "5") (pinfunction "NC_5") (pintype "bidirectional"))
    )
    (net (code "65") (name "unconnected-(IC7-{slash}INT-Pad4)") (class "Default")
      (node (ref "IC7") (pin "4") (pinfunction "/INT_4") (pintype "bidirectional"))
    )
    (net (code "66") (name "unconnected-(MICROSD-NC-Pad1)") (class "Default")
      (node (ref "MICROSD") (pin "1") (pinfunction "NC_1") (pintype "bidirectional"))
    )
    (net (code "67") (name "unconnected-(MICROSD-RSV-Pad8)") (class "Default")
      (node (ref "MICROSD") (pin "8") (pinfunction "RSV_8") (pintype "bidirectional"))
    )
    (net (code "68") (name "unconnected-(N5110-Pad8)") (class "Default")
      (node (ref "N5110") (pin "8") (pinfunction "8_8") (pintype "passive"))
    )
    (net (code "69") (name "unconnected-(RJ45-PadNC)") (class "Default")
      (node (ref "RJ45") (pin "NC") (pinfunction "NC_NC") (pintype "bidirectional"))
    )
    (net (code "70") (name "unconnected-(RJ45-PadP5)") (class "Default")
      (node (ref "RJ45") (pin "P5") (pinfunction "P5_P5") (pintype "bidirectional"))
    )
    (net (code "71") (name "unconnected-(RTC-SQW{slash}OUT-Pad7)") (class "Default")
      (node (ref "RTC") (pin "7") (pinfunction "SQW/OUT_7") (pintype "bidirectional"))
    )
    (net (code "72") (name "unconnected-(U$1-EOC-PadP$2)") (class "Default")
      (node (ref "U$1") (pin "P$2") (pinfunction "EOC_P$2") (pintype "bidirectional"))
    )
  )
)
